# Output_stages.net
KiCad netlist of a schematic drawn in Altium Designer
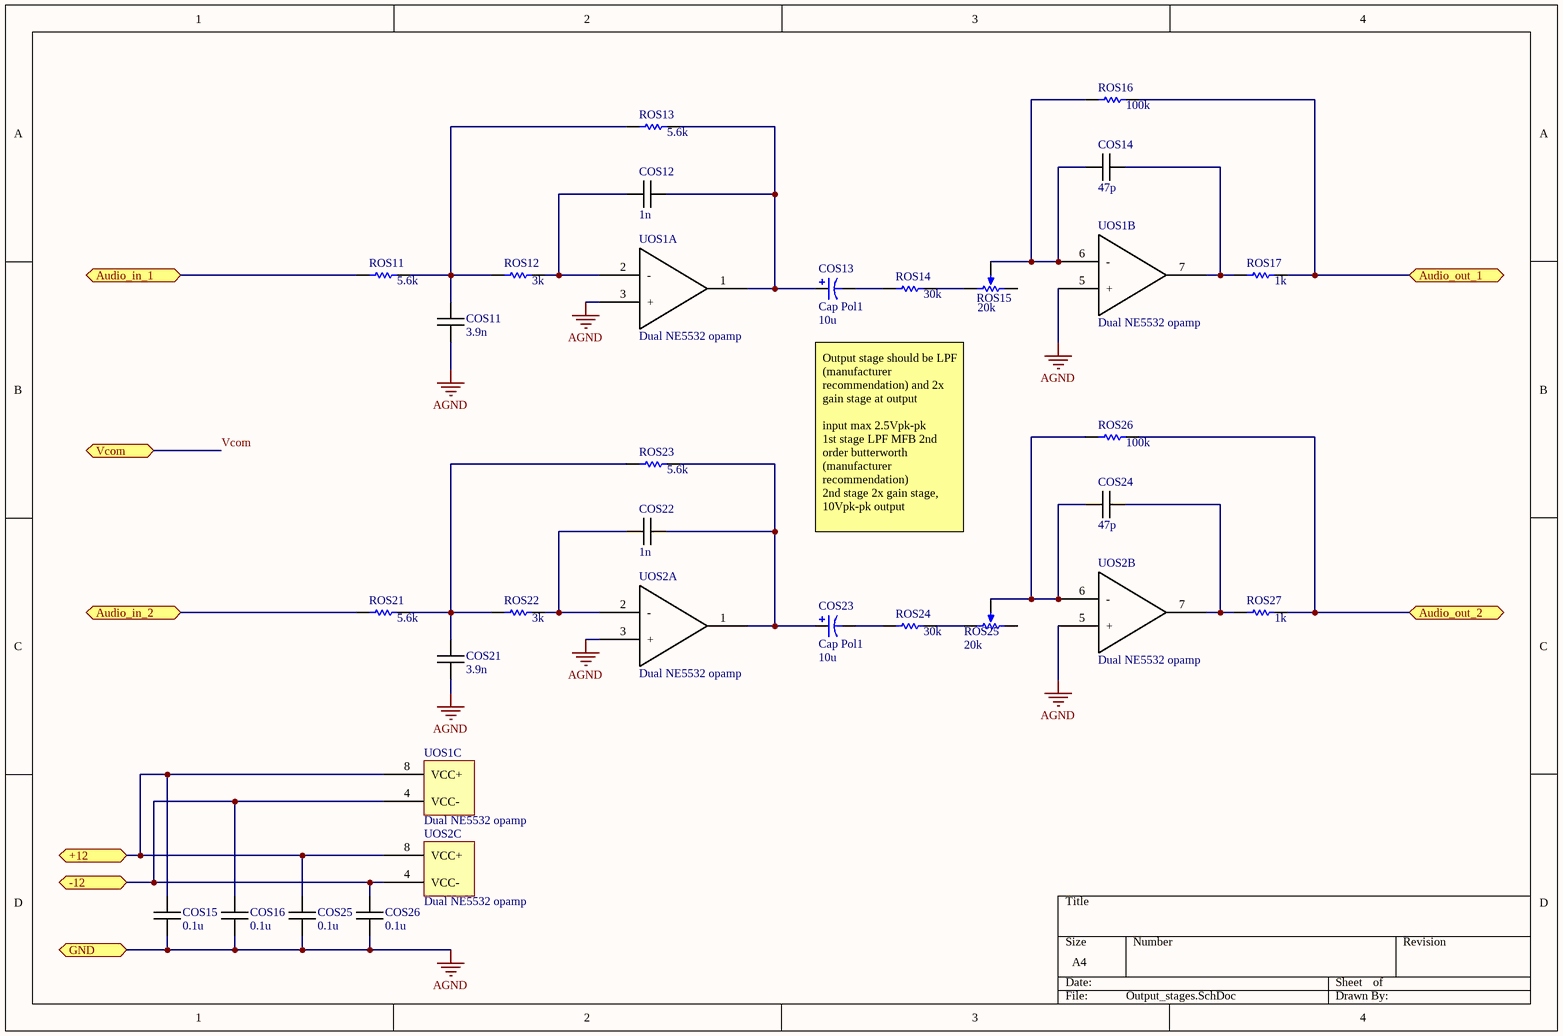
[diagram p0: Output_stages.SchDoc]

(export (version "E")
  (design (tool "Eeschema 10.0.6"))
  (components
    (comp (ref "COS11")
      (value "3.9n")
      (footprint "C 0603 / 1608")
      (libsource (lib "Standard") (part "Capacitor"))
    )
    (comp (ref "COS12")
      (value "1n")
      (footprint "C 0603 / 1608")
      (libsource (lib "Standard") (part "Capacitor"))
    )
    (comp (ref "COS13")
      (value "Cap Pol1")
      (footprint "RB7.6-15")
      (description "Polarized Capacitor (Radial)")
      (fields (field (name "ALTIUM_VALUE") "10u") (field (name "PUBLISHER") "Altium Limited"))
      (libsource (lib "Miscellaneous Devices") (part "Cap Pol1"))
    )
    (comp (ref "COS14")
      (value "47p")
      (footprint "C 0603 / 1608")
      (libsource (lib "Standard") (part "Capacitor"))
    )
    (comp (ref "COS15")
      (value "0.1u")
      (footprint "C 0603 / 1608")
      (libsource (lib "Standard") (part "Capacitor"))
    )
    (comp (ref "COS16")
      (value "0.1u")
      (footprint "C 0603 / 1608")
      (libsource (lib "Standard") (part "Capacitor"))
    )
    (comp (ref "COS21")
      (value "3.9n")
      (footprint "C 0603 / 1608")
      (libsource (lib "Standard") (part "Capacitor"))
    )
    (comp (ref "COS22")
      (value "1n")
      (footprint "C 0603 / 1608")
      (libsource (lib "Standard") (part "Capacitor"))
    )
    (comp (ref "COS23")
      (value "Cap Pol1")
      (footprint "RB7.6-15")
      (description "Polarized Capacitor (Radial)")
      (fields (field (name "ALTIUM_VALUE") "10u") (field (name "PUBLISHER") "Altium Limited"))
      (libsource (lib "Miscellaneous Devices") (part "Cap Pol1"))
    )
    (comp (ref "COS24")
      (value "47p")
      (footprint "C 0603 / 1608")
      (libsource (lib "Standard") (part "Capacitor"))
    )
    (comp (ref "COS25")
      (value "0.1u")
      (footprint "C 0603 / 1608")
      (libsource (lib "Standard") (part "Capacitor"))
    )
    (comp (ref "COS26")
      (value "0.1u")
      (footprint "C 0603 / 1608")
      (libsource (lib "Standard") (part "Capacitor"))
    )
    (comp (ref "ROS11")
      (value "5.6k")
      (footprint "RES0603R")
      (description "Resistor")
      (fields (field (name "PUBLISHER") "Altium Limited"))
      (libsource (lib "Standard") (part "Res1"))
    )
    (comp (ref "ROS12")
      (value "3k")
      (footprint "RES0603R")
      (description "Resistor")
      (fields (field (name "PUBLISHER") "Altium Limited"))
      (libsource (lib "Standard") (part "Res1"))
    )
    (comp (ref "ROS13")
      (value "5.6k")
      (footprint "RES0603R")
      (description "Resistor")
      (fields (field (name "PUBLISHER") "Altium Limited"))
      (libsource (lib "Standard") (part "Res1"))
    )
    (comp (ref "ROS14")
      (value "30k")
      (footprint "RES0603R")
      (description "Resistor")
      (fields (field (name "PUBLISHER") "Altium Limited"))
      (libsource (lib "Standard") (part "Res1"))
    )
    (comp (ref "ROS15")
      (value "20k")
      (footprint "SMD_POT_3x3mm")
      (description "Potentiometer")
      (fields (field (name "PUBLISHER") "Altium Limited"))
      (libsource (lib "Standard") (part "RPot"))
    )
    (comp (ref "ROS16")
      (value "100k")
      (footprint "RES0603R")
      (description "Resistor")
      (fields (field (name "PUBLISHER") "Altium Limited"))
      (libsource (lib "Standard") (part "Res1"))
    )
    (comp (ref "ROS17")
      (value "1k")
      (footprint "RES0603R")
      (description "Resistor")
      (fields (field (name "PUBLISHER") "Altium Limited"))
      (libsource (lib "Standard") (part "Res1"))
    )
    (comp (ref "ROS21")
      (value "5.6k")
      (footprint "RES0603R")
      (description "Resistor")
      (fields (field (name "PUBLISHER") "Altium Limited"))
      (libsource (lib "Standard") (part "Res1"))
    )
    (comp (ref "ROS22")
      (value "3k")
      (footprint "RES0603R")
      (description "Resistor")
      (fields (field (name "PUBLISHER") "Altium Limited"))
      (libsource (lib "Standard") (part "Res1"))
    )
    (comp (ref "ROS23")
      (value "5.6k")
      (footprint "RES0603R")
      (description "Resistor")
      (fields (field (name "PUBLISHER") "Altium Limited"))
      (libsource (lib "Standard") (part "Res1"))
    )
    (comp (ref "ROS24")
      (value "30k")
      (footprint "RES0603R")
      (description "Resistor")
      (fields (field (name "PUBLISHER") "Altium Limited"))
      (libsource (lib "Standard") (part "Res1"))
    )
    (comp (ref "ROS25")
      (value "20k")
      (footprint "SMD_POT_3x3mm")
      (description "Potentiometer")
      (fields (field (name "PUBLISHER") "Altium Limited"))
      (libsource (lib "Standard") (part "RPot"))
    )
    (comp (ref "ROS26")
      (value "100k")
      (footprint "RES0603R")
      (description "Resistor")
      (fields (field (name "PUBLISHER") "Altium Limited"))
      (libsource (lib "Standard") (part "Res1"))
    )
    (comp (ref "ROS27")
      (value "1k")
      (footprint "RES0603R")
      (description "Resistor")
      (fields (field (name "PUBLISHER") "Altium Limited"))
      (libsource (lib "Standard") (part "Res1"))
    )
    (comp (ref "UOS1") (value "Dual NE5532 opamp") (libsource (lib "") (part "NE5532_1")))
    (comp (ref "UOS2") (value "Dual NE5532 opamp") (libsource (lib "") (part "NE5532_1")))
  )
  (nets
    (net (code "1") (name "/+12") (class "Default")
      (node (ref "COS15") (pin "2") (pinfunction "1_2") (pintype "passive"))
      (node (ref "COS25") (pin "2") (pinfunction "1_2") (pintype "passive"))
      (node (ref "UOS1") (pin "8") (pinfunction "VCC+_8") (pintype "passive"))
      (node (ref "UOS2") (pin "8") (pinfunction "VCC+_8") (pintype "passive"))
    )
    (net (code "2") (name "/-12") (class "Default")
      (node (ref "COS16") (pin "2") (pinfunction "1_2") (pintype "passive"))
      (node (ref "COS26") (pin "2") (pinfunction "1_2") (pintype "passive"))
      (node (ref "UOS1") (pin "4") (pinfunction "VCC-_4") (pintype "passive"))
      (node (ref "UOS2") (pin "4") (pinfunction "VCC-_4") (pintype "passive"))
    )
    (net (code "3") (name "/Audio_in_1") (class "Default")
      (node (ref "ROS11") (pin "1") (pinfunction "1_1") (pintype "passive"))
    )
    (net (code "4") (name "/Audio_in_2") (class "Default")
      (node (ref "ROS21") (pin "1") (pinfunction "1_1") (pintype "passive"))
    )
    (net (code "5") (name "/Audio_out_1") (class "Default")
      (node (ref "ROS16") (pin "2") (pinfunction "2_2") (pintype "passive"))
      (node (ref "ROS17") (pin "2") (pinfunction "2_2") (pintype "passive"))
    )
    (net (code "6") (name "/Audio_out_2") (class "Default")
      (node (ref "ROS26") (pin "2") (pinfunction "2_2") (pintype "passive"))
      (node (ref "ROS27") (pin "2") (pinfunction "2_2") (pintype "passive"))
    )
    (net (code "8") (name "AGND") (class "Default")
      (node (ref "COS11") (pin "1") (pinfunction "1_1") (pintype "passive"))
      (node (ref "COS15") (pin "1") (pinfunction "1_1") (pintype "passive"))
      (node (ref "COS16") (pin "1") (pinfunction "1_1") (pintype "passive"))
      (node (ref "COS21") (pin "1") (pinfunction "1_1") (pintype "passive"))
      (node (ref "COS25") (pin "1") (pinfunction "1_1") (pintype "passive"))
      (node (ref "COS26") (pin "1") (pinfunction "1_1") (pintype "passive"))
      (node (ref "UOS1") (pin "3") (pinfunction "+_3") (pintype "passive"))
      (node (ref "UOS1") (pin "5") (pinfunction "+_5") (pintype "passive"))
      (node (ref "UOS2") (pin "3") (pinfunction "+_3") (pintype "passive"))
      (node (ref "UOS2") (pin "5") (pinfunction "+_5") (pintype "passive"))
    )
    (net (code "9") (name "Net-(COS11-1-Pad2)") (class "Default")
      (node (ref "COS11") (pin "2") (pinfunction "1_2") (pintype "passive"))
      (node (ref "ROS11") (pin "2") (pinfunction "2_2") (pintype "passive"))
      (node (ref "ROS12") (pin "1") (pinfunction "1_1") (pintype "passive"))
      (node (ref "ROS13") (pin "1") (pinfunction "1_1") (pintype "passive"))
    )
    (net (code "10") (name "Net-(COS13-Pad2)") (class "Default")
      (node (ref "COS13") (pin "2") (pinfunction "2_2") (pintype "passive"))
      (node (ref "ROS14") (pin "1") (pinfunction "1_1") (pintype "passive"))
    )
    (net (code "11") (name "Net-(COS21-1-Pad2)") (class "Default")
      (node (ref "COS21") (pin "2") (pinfunction "1_2") (pintype "passive"))
      (node (ref "ROS21") (pin "2") (pinfunction "2_2") (pintype "passive"))
      (node (ref "ROS22") (pin "1") (pinfunction "1_1") (pintype "passive"))
      (node (ref "ROS23") (pin "1") (pinfunction "1_1") (pintype "passive"))
    )
    (net (code "12") (name "Net-(COS23-Pad2)") (class "Default")
      (node (ref "COS23") (pin "2") (pinfunction "2_2") (pintype "passive"))
      (node (ref "ROS24") (pin "1") (pinfunction "1_1") (pintype "passive"))
    )
    (net (code "13") (name "Net-(ROS15-BOT)") (class "Default")
      (node (ref "ROS14") (pin "2") (pinfunction "2_2") (pintype "passive"))
      (node (ref "ROS15") (pin "2") (pinfunction "BOT_2") (pintype "passive"))
    )
    (net (code "14") (name "Net-(ROS15-TAP)") (class "Default")
      (node (ref "COS14") (pin "1") (pinfunction "1_1") (pintype "passive"))
      (node (ref "ROS15") (pin "3") (pinfunction "TAP_3") (pintype "passive"))
      (node (ref "ROS16") (pin "1") (pinfunction "1_1") (pintype "passive"))
      (node (ref "UOS1") (pin "6") (pinfunction "-_6") (pintype "passive"))
    )
    (net (code "15") (name "Net-(ROS25-BOT)") (class "Default")
      (node (ref "ROS24") (pin "2") (pinfunction "2_2") (pintype "passive"))
      (node (ref "ROS25") (pin "2") (pinfunction "BOT_2") (pintype "passive"))
    )
    (net (code "16") (name "Net-(ROS25-TAP)") (class "Default")
      (node (ref "COS24") (pin "1") (pinfunction "1_1") (pintype "passive"))
      (node (ref "ROS25") (pin "3") (pinfunction "TAP_3") (pintype "passive"))
      (node (ref "ROS26") (pin "1") (pinfunction "1_1") (pintype "passive"))
      (node (ref "UOS2") (pin "6") (pinfunction "-_6") (pintype "passive"))
    )
    (net (code "17") (name "Net-(UOS1A--)") (class "Default")
      (node (ref "COS12") (pin "1") (pinfunction "1_1") (pintype "passive"))
      (node (ref "ROS12") (pin "2") (pinfunction "2_2") (pintype "passive"))
      (node (ref "UOS1") (pin "2") (pinfunction "-_2") (pintype "passive"))
    )
    (net (code "18") (name "Net-(UOS1A-OUT)") (class "Default")
      (node (ref "COS12") (pin "2") (pinfunction "1_2") (pintype "passive"))
      (node (ref "COS13") (pin "1") (pinfunction "1_1") (pintype "passive"))
      (node (ref "ROS13") (pin "2") (pinfunction "2_2") (pintype "passive"))
      (node (ref "UOS1") (pin "1") (pinfunction "OUT_1") (pintype "passive"))
    )
    (net (code "19") (name "Net-(UOS1B-OUT)") (class "Default")
      (node (ref "COS14") (pin "2") (pinfunction "1_2") (pintype "passive"))
      (node (ref "ROS17") (pin "1") (pinfunction "1_1") (pintype "passive"))
      (node (ref "UOS1") (pin "7") (pinfunction "OUT_7") (pintype "passive"))
    )
    (net (code "20") (name "Net-(UOS2A--)") (class "Default")
      (node (ref "COS22") (pin "1") (pinfunction "1_1") (pintype "passive"))
      (node (ref "ROS22") (pin "2") (pinfunction "2_2") (pintype "passive"))
      (node (ref "UOS2") (pin "2") (pinfunction "-_2") (pintype "passive"))
    )
    (net (code "21") (name "Net-(UOS2A-OUT)") (class "Default")
      (node (ref "COS22") (pin "2") (pinfunction "1_2") (pintype "passive"))
      (node (ref "COS23") (pin "1") (pinfunction "1_1") (pintype "passive"))
      (node (ref "ROS23") (pin "2") (pinfunction "2_2") (pintype "passive"))
      (node (ref "UOS2") (pin "1") (pinfunction "OUT_1") (pintype "passive"))
    )
    (net (code "22") (name "Net-(UOS2B-OUT)") (class "Default")
      (node (ref "COS24") (pin "2") (pinfunction "1_2") (pintype "passive"))
      (node (ref "ROS27") (pin "1") (pinfunction "1_1") (pintype "passive"))
      (node (ref "UOS2") (pin "7") (pinfunction "OUT_7") (pintype "passive"))
    )
    (net (code "23") (name "unconnected-(ROS15-TOP-Pad1)") (class "Default")
      (node (ref "ROS15") (pin "1") (pinfunction "TOP_1") (pintype "passive"))
    )
    (net (code "24") (name "unconnected-(ROS25-TOP-Pad1)") (class "Default")
      (node (ref "ROS25") (pin "1") (pinfunction "TOP_1") (pintype "passive"))
    )
  )
)
